# RS485_Breakout.net
KiCad netlist of a schematic drawn in EAGLE
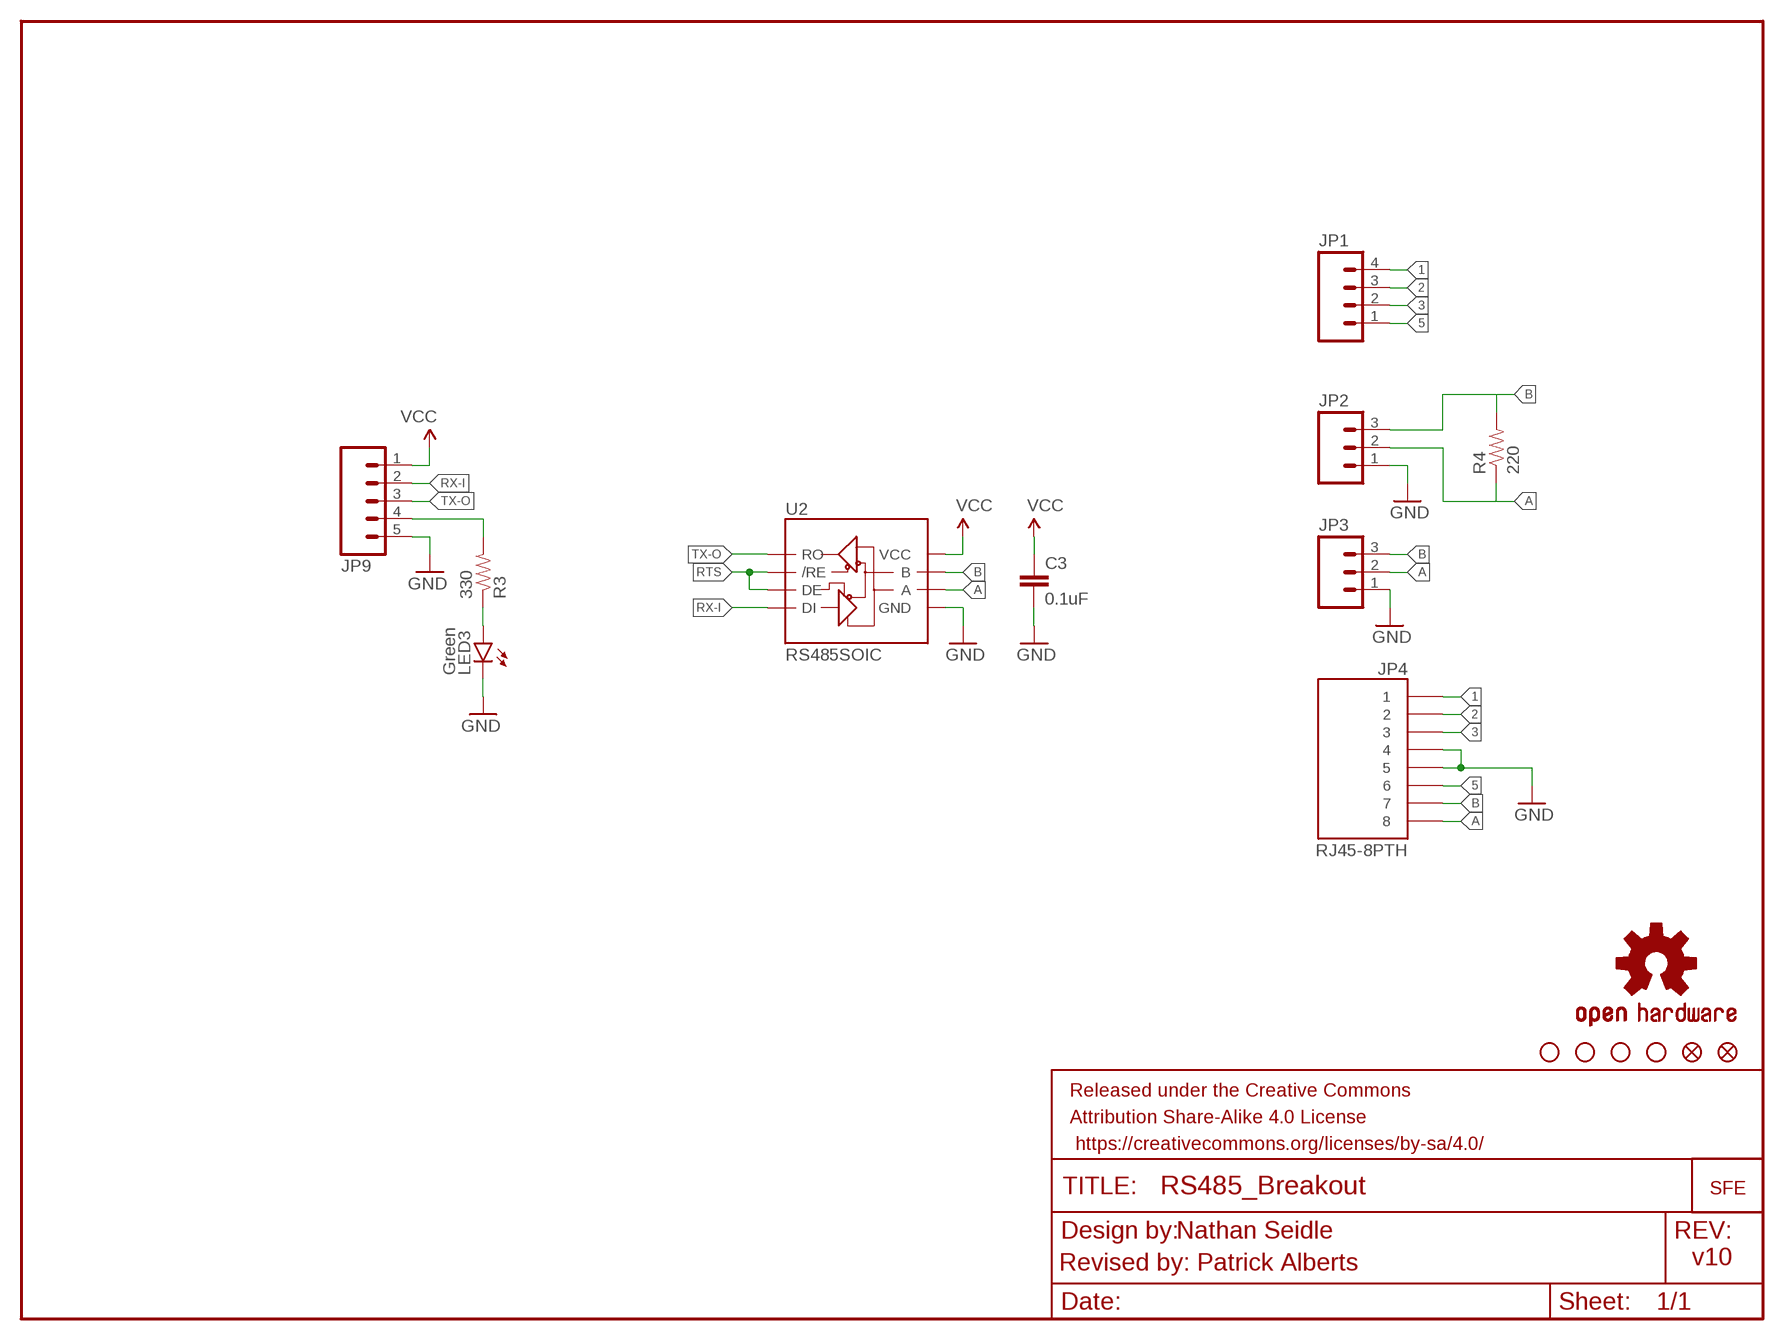
[diagram p0: schematic, sheet 1]

(export (version "E")
  (design (tool "Eeschema 10.0.6"))
  (components
    (comp (ref "C3")
      (value "0.1uF")
      (footprint "eagle-import:0603-CAP")
      (libsource (lib "eagle-import") (part "0.1UF-25V(+80/-20%)(0603)"))
    )
    (comp (ref "FRAME1")
      (value "FRAME-LETTER")
      (footprint "eagle-import:CREATIVE_COMMONS")
      (libsource (lib "eagle-import") (part "FRAME-LETTER"))
    )
    (comp (ref "JP1")
      (value "M04PTH")
      (footprint "eagle-import:1X04")
      (libsource (lib "eagle-import") (part "M04PTH"))
    )
    (comp (ref "JP2")
      (value "M03SCREW")
      (footprint "eagle-import:SCREWTERMINAL-3.5MM-3")
      (libsource (lib "eagle-import") (part "M03SCREW"))
    )
    (comp (ref "JP3")
      (value "M03PTH")
      (footprint "eagle-import:1X03")
      (libsource (lib "eagle-import") (part "M03PTH"))
    )
    (comp (ref "JP4")
      (value "RJ45-8PTH")
      (footprint "eagle-import:RJ45-8")
      (libsource (lib "eagle-import") (part "RJ45-8PTH"))
    )
    (comp (ref "JP5")
      (value "FIDUCIAL1X2")
      (footprint "eagle-import:FIDUCIAL-1X2")
      (libsource (lib "eagle-import") (part "FIDUCIAL1X2"))
    )
    (comp (ref "JP6")
      (value "STAND-OFF")
      (footprint "eagle-import:STAND-OFF")
      (libsource (lib "eagle-import") (part "STAND-OFF"))
    )
    (comp (ref "JP7")
      (value "STAND-OFF")
      (footprint "eagle-import:STAND-OFF")
      (libsource (lib "eagle-import") (part "STAND-OFF"))
    )
    (comp (ref "JP8")
      (value "STAND-OFF")
      (footprint "eagle-import:STAND-OFF")
      (libsource (lib "eagle-import") (part "STAND-OFF"))
    )
    (comp (ref "JP9")
      (value "M05PTH")
      (footprint "eagle-import:1X05")
      (libsource (lib "eagle-import") (part "M05PTH"))
    )
    (comp (ref "JP10")
      (value "FIDUCIAL1X2")
      (footprint "eagle-import:FIDUCIAL-1X2")
      (libsource (lib "eagle-import") (part "FIDUCIAL1X2"))
    )
    (comp (ref "JP15")
      (value "STAND-OFF")
      (footprint "eagle-import:STAND-OFF")
      (libsource (lib "eagle-import") (part "STAND-OFF"))
    )
    (comp (ref "LED3")
      (value "Green")
      (footprint "eagle-import:LED-0603")
      (libsource (lib "eagle-import") (part "LED-GREEN0603"))
    )
    (comp (ref "LOGO1")
      (value "OSHW-LOGOS")
      (footprint "eagle-import:OSHW-LOGO-S")
      (libsource (lib "eagle-import") (part "OSHW-LOGOS"))
    )
    (comp (ref "R3")
      (value "330")
      (footprint "eagle-import:0603-RES")
      (libsource (lib "eagle-import") (part "330OHM1/10W1%(0603)"))
    )
    (comp (ref "R4")
      (value "220")
      (footprint "eagle-import:0603-RES")
      (libsource (lib "eagle-import") (part "22OHM1/10W1%(0603)"))
    )
    (comp (ref "U$2")
      (value "LOGO-SFESK")
      (footprint "eagle-import:SFE-LOGO-FLAME")
      (libsource (lib "eagle-import") (part "LOGO-SFESK"))
    )
    (comp (ref "U2")
      (value "RS485SOIC")
      (footprint "eagle-import:SO08")
      (libsource (lib "eagle-import") (part "RS485SOIC"))
    )
  )
  (nets
    (net (code "1") (name "1") (class "Default")
      (node (ref "JP1") (pin "4") (pinfunction "4_4") (pintype "passive"))
      (node (ref "JP4") (pin "1") (pinfunction "1_1") (pintype "bidirectional"))
    )
    (net (code "2") (name "2") (class "Default")
      (node (ref "JP1") (pin "3") (pinfunction "3_3") (pintype "passive"))
      (node (ref "JP4") (pin "2") (pinfunction "2_2") (pintype "bidirectional"))
    )
    (net (code "3") (name "3") (class "Default")
      (node (ref "JP1") (pin "2") (pinfunction "2_2") (pintype "passive"))
      (node (ref "JP4") (pin "3") (pinfunction "3_3") (pintype "bidirectional"))
    )
    (net (code "4") (name "5") (class "Default")
      (node (ref "JP1") (pin "1") (pinfunction "1_1") (pintype "passive"))
      (node (ref "JP4") (pin "6") (pinfunction "6_6") (pintype "bidirectional"))
    )
    (net (code "5") (name "A") (class "Default")
      (node (ref "JP2") (pin "2") (pinfunction "2_2") (pintype "passive"))
      (node (ref "JP3") (pin "2") (pinfunction "2_2") (pintype "passive"))
      (node (ref "JP4") (pin "8") (pinfunction "8_8") (pintype "bidirectional"))
      (node (ref "R4") (pin "1") (pinfunction "1_1") (pintype "passive"))
      (node (ref "U2") (pin "6") (pinfunction "A_6") (pintype "bidirectional"))
    )
    (net (code "6") (name "B") (class "Default")
      (node (ref "JP2") (pin "3") (pinfunction "3_3") (pintype "passive"))
      (node (ref "JP3") (pin "3") (pinfunction "3_3") (pintype "passive"))
      (node (ref "JP4") (pin "7") (pinfunction "7_7") (pintype "bidirectional"))
      (node (ref "R4") (pin "2") (pinfunction "2_2") (pintype "passive"))
      (node (ref "U2") (pin "7") (pinfunction "B_7") (pintype "bidirectional"))
    )
    (net (code "7") (name "GND") (class "Default")
      (node (ref "C3") (pin "2") (pinfunction "2_2") (pintype "passive"))
      (node (ref "JP2") (pin "1") (pinfunction "1_1") (pintype "passive"))
      (node (ref "JP3") (pin "1") (pinfunction "1_1") (pintype "passive"))
      (node (ref "JP4") (pin "4") (pinfunction "4_4") (pintype "bidirectional"))
      (node (ref "JP4") (pin "5") (pinfunction "5_5") (pintype "bidirectional"))
      (node (ref "JP9") (pin "5") (pinfunction "5_5") (pintype "passive"))
      (node (ref "LED3") (pin "C") (pinfunction "C_C") (pintype "passive"))
      (node (ref "U2") (pin "5") (pinfunction "GND_5") (pintype "bidirectional"))
    )
    (net (code "8") (name "Net-(LED3-PadA)") (class "Default")
      (node (ref "LED3") (pin "A") (pinfunction "A_A") (pintype "passive"))
      (node (ref "R3") (pin "1") (pinfunction "1_1") (pintype "passive"))
    )
    (net (code "9") (name "RTS") (class "Default")
      (node (ref "JP9") (pin "4") (pinfunction "4_4") (pintype "passive"))
      (node (ref "R3") (pin "2") (pinfunction "2_2") (pintype "passive"))
      (node (ref "U2") (pin "2") (pinfunction "/RE_2") (pintype "bidirectional"))
      (node (ref "U2") (pin "3") (pinfunction "DE_3") (pintype "bidirectional"))
    )
    (net (code "10") (name "RX-I") (class "Default")
      (node (ref "JP9") (pin "2") (pinfunction "2_2") (pintype "passive"))
      (node (ref "U2") (pin "4") (pinfunction "DI_4") (pintype "bidirectional"))
    )
    (net (code "11") (name "TX-O") (class "Default")
      (node (ref "JP9") (pin "3") (pinfunction "3_3") (pintype "passive"))
      (node (ref "U2") (pin "1") (pinfunction "RO_1") (pintype "bidirectional"))
    )
    (net (code "12") (name "VCC") (class "Default")
      (node (ref "C3") (pin "1") (pinfunction "1_1") (pintype "passive"))
      (node (ref "JP9") (pin "1") (pinfunction "1_1") (pintype "passive"))
      (node (ref "U2") (pin "8") (pinfunction "VCC_8") (pintype "bidirectional"))
    )
  )
)
